# supply.net
KiCad netlist of a schematic drawn in EAGLE
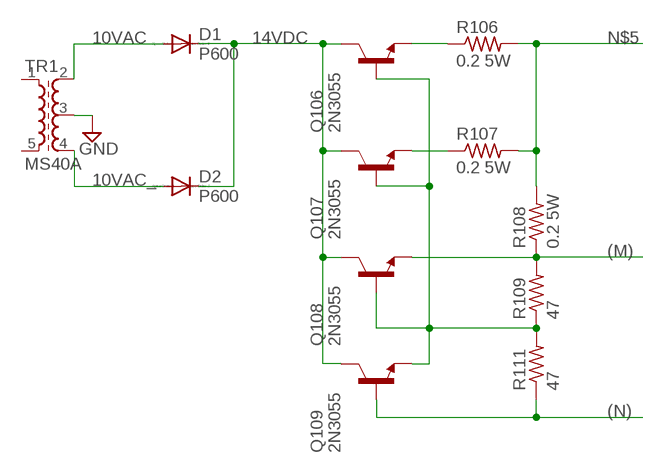
[diagram p0: schematic, sheet 1]

(export (version "E")
  (design (tool "Eeschema 10.0.6"))
  (components
    (comp (ref "D1")
      (value "P600")
      (footprint "eagle-import:P6-15")
      (libsource (lib "eagle-import") (part "P600"))
    )
    (comp (ref "D2")
      (value "P600")
      (footprint "eagle-import:P6-15")
      (libsource (lib "eagle-import") (part "P600"))
    )
    (comp (ref "Q106")
      (value "2N3055")
      (footprint "eagle-import:TO3")
      (libsource (lib "eagle-import") (part "2N3055"))
    )
    (comp (ref "Q107")
      (value "2N3055")
      (footprint "eagle-import:TO3")
      (libsource (lib "eagle-import") (part "2N3055"))
    )
    (comp (ref "Q108")
      (value "2N3055")
      (footprint "eagle-import:TO3")
      (libsource (lib "eagle-import") (part "2N3055"))
    )
    (comp (ref "Q109")
      (value "2N3055")
      (footprint "eagle-import:TO3")
      (libsource (lib "eagle-import") (part "2N3055"))
    )
    (comp (ref "R106")
      (value "0.2 5W")
      (footprint "eagle-import:0617_17")
      (libsource (lib "eagle-import") (part "R-US_0617/17"))
    )
    (comp (ref "R107")
      (value "0.2 5W")
      (footprint "eagle-import:0617_17")
      (libsource (lib "eagle-import") (part "R-US_0617/17"))
    )
    (comp (ref "R108")
      (value "0.2 5W")
      (footprint "eagle-import:0617_17")
      (libsource (lib "eagle-import") (part "R-US_0617/17"))
    )
    (comp (ref "R109")
      (value "47")
      (footprint "eagle-import:0207_10")
      (libsource (lib "eagle-import") (part "R-US_0207/10"))
    )
    (comp (ref "R111")
      (value "47")
      (footprint "eagle-import:0207_10")
      (libsource (lib "eagle-import") (part "R-US_0207/10"))
    )
    (comp (ref "TR1")
      (value "MS40A")
      (footprint "eagle-import:MS40")
      (libsource (lib "eagle-import") (part "MS40A"))
    )
  )
  (nets
    (net (code "1") (name "/(M)") (class "Default")
      (node (ref "Q108") (pin "E") (pinfunction "E_E") (pintype "passive"))
      (node (ref "R108") (pin "1") (pinfunction "1_1") (pintype "passive"))
      (node (ref "R109") (pin "2") (pinfunction "2_2") (pintype "passive"))
    )
    (net (code "2") (name "/(N)") (class "Default")
      (node (ref "Q109") (pin "B") (pinfunction "B_B") (pintype "passive"))
      (node (ref "R111") (pin "1") (pinfunction "1_1") (pintype "passive"))
    )
    (net (code "3") (name "/10VAC") (class "Default")
      (node (ref "D1") (pin "A") (pinfunction "A_A") (pintype "passive"))
      (node (ref "TR1") (pin "2") (pinfunction "2_2") (pintype "passive"))
    )
    (net (code "4") (name "/10VAC_") (class "Default")
      (node (ref "D2") (pin "A") (pinfunction "A_A") (pintype "passive"))
      (node (ref "TR1") (pin "4") (pinfunction "4_4") (pintype "passive"))
    )
    (net (code "5") (name "/14VDC") (class "Default")
      (node (ref "D1") (pin "C") (pinfunction "C_C") (pintype "passive"))
      (node (ref "D2") (pin "C") (pinfunction "C_C") (pintype "passive"))
      (node (ref "Q106") (pin "C") (pinfunction "C_C") (pintype "passive"))
      (node (ref "Q106") (pin "C/") (pinfunction "C_C/") (pintype "passive"))
      (node (ref "Q107") (pin "C") (pinfunction "C_C") (pintype "passive"))
      (node (ref "Q107") (pin "C/") (pinfunction "C_C/") (pintype "passive"))
      (node (ref "Q108") (pin "C") (pinfunction "C_C") (pintype "passive"))
      (node (ref "Q108") (pin "C/") (pinfunction "C_C/") (pintype "passive"))
      (node (ref "Q109") (pin "C") (pinfunction "C_C") (pintype "passive"))
      (node (ref "Q109") (pin "C/") (pinfunction "C_C/") (pintype "passive"))
    )
    (net (code "6") (name "/N$5") (class "Default")
      (node (ref "R106") (pin "2") (pinfunction "2_2") (pintype "passive"))
      (node (ref "R107") (pin "2") (pinfunction "2_2") (pintype "passive"))
      (node (ref "R108") (pin "2") (pinfunction "2_2") (pintype "passive"))
    )
    (net (code "7") (name "GND") (class "Default")
      (node (ref "TR1") (pin "3") (pinfunction "3_3") (pintype "passive"))
    )
    (net (code "8") (name "Net-(Q106-PadB)") (class "Default")
      (node (ref "Q106") (pin "B") (pinfunction "B_B") (pintype "passive"))
      (node (ref "Q107") (pin "B") (pinfunction "B_B") (pintype "passive"))
      (node (ref "Q108") (pin "B") (pinfunction "B_B") (pintype "passive"))
      (node (ref "Q109") (pin "E") (pinfunction "E_E") (pintype "passive"))
      (node (ref "R109") (pin "1") (pinfunction "1_1") (pintype "passive"))
      (node (ref "R111") (pin "2") (pinfunction "2_2") (pintype "passive"))
    )
    (net (code "9") (name "Net-(Q106-PadE)") (class "Default")
      (node (ref "Q106") (pin "E") (pinfunction "E_E") (pintype "passive"))
      (node (ref "R106") (pin "1") (pinfunction "1_1") (pintype "passive"))
    )
    (net (code "10") (name "Net-(Q107-PadE)") (class "Default")
      (node (ref "Q107") (pin "E") (pinfunction "E_E") (pintype "passive"))
      (node (ref "R107") (pin "1") (pinfunction "1_1") (pintype "passive"))
    )
    (net (code "11") (name "unconnected-(TR1-Pad1)") (class "Default")
      (node (ref "TR1") (pin "1") (pinfunction "1_1") (pintype "passive"))
    )
    (net (code "12") (name "unconnected-(TR1-Pad5)") (class "Default")
      (node (ref "TR1") (pin "5") (pinfunction "5_5") (pintype "passive"))
    )
  )
)
